# Sheet.net
KiCad netlist of a schematic drawn in Altium Designer
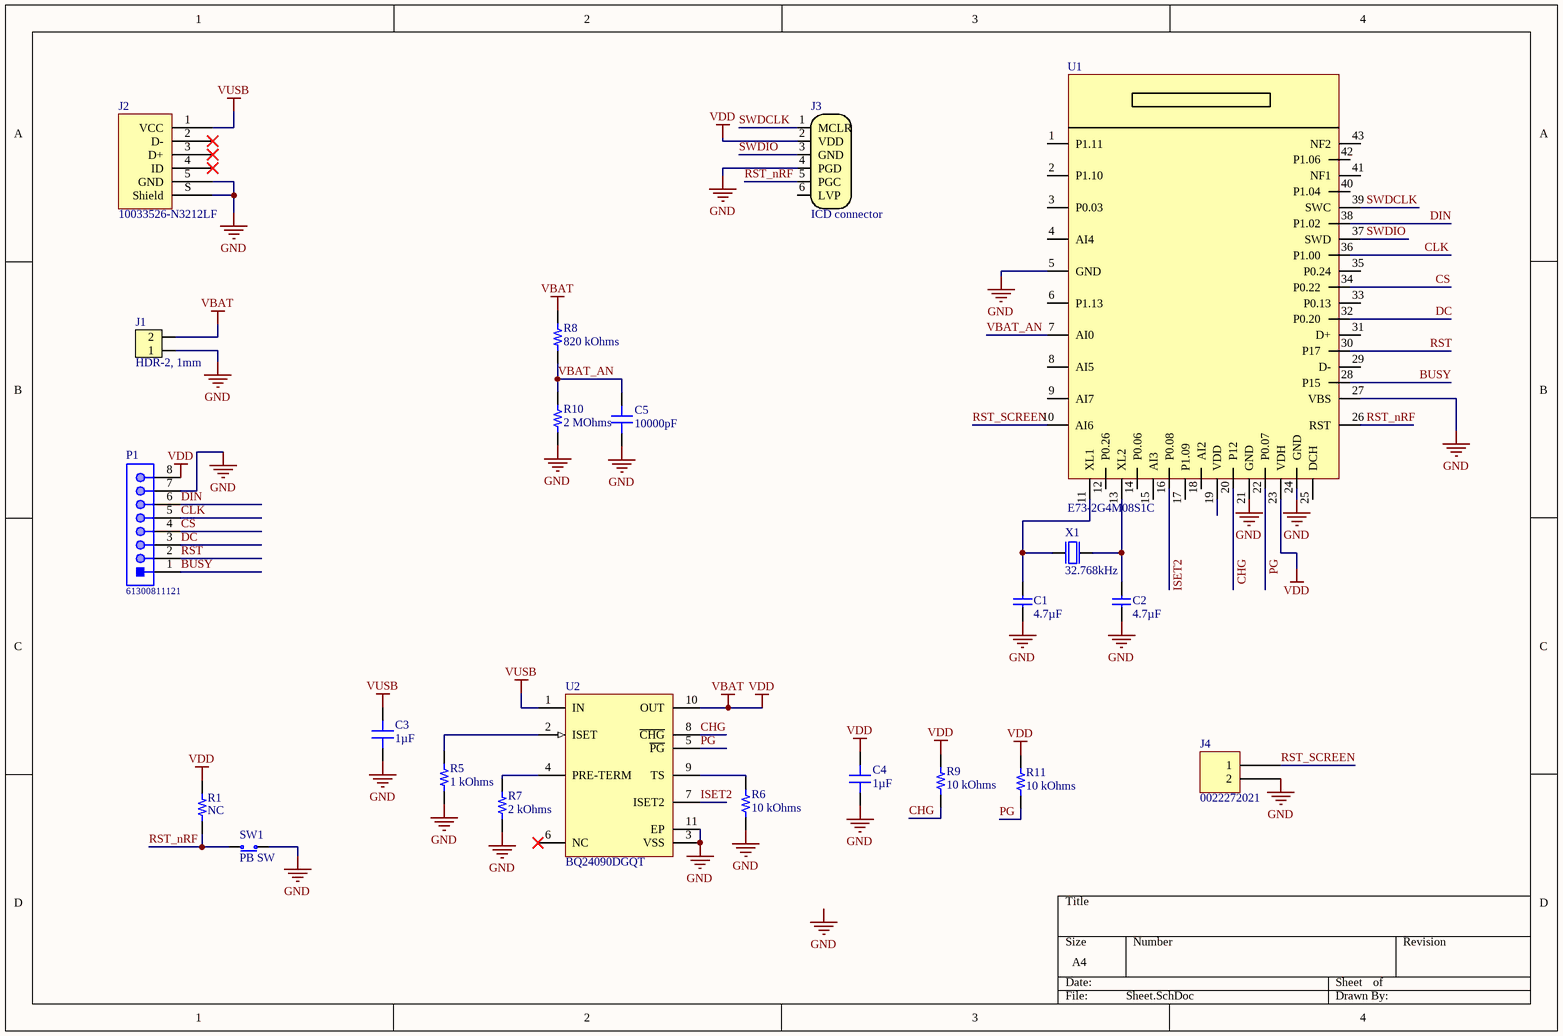
[diagram p0: Sheet.SchDoc]

(export (version "E")
  (design (tool "Eeschema 10.0.6"))
  (components
    (comp (ref "C1")
      (value "4.7µF")
      (footprint "CAPC1608X06L")
      (description "Capacitor, X7R, ±10%")
      (fields
        (field (name "PART NUMBER") "C0603-4µ7-6.3V-X7R")
        (field (name "MANUFACTURER") "Samsung")
        (field (name "PUBLISHER") "Nordic Semiconductor")
      )
      (libsource (lib "pca10056") (part "CAP_0603"))
    )
    (comp (ref "C2")
      (value "4.7µF")
      (footprint "CAPC1608X06L")
      (description "Capacitor, X7R, ±10%")
      (fields
        (field (name "PART NUMBER") "C0603-4µ7-6.3V-X7R")
        (field (name "MANUFACTURER") "Samsung")
        (field (name "PUBLISHER") "Nordic Semiconductor")
      )
      (libsource (lib "pca10056") (part "CAP_0603"))
    )
    (comp (ref "C3")
      (value "1µF")
      (footprint "CAP 0603_1608")
      (description "CAP CER 1UF 6.3V X5R 0603")
      (fields (field (name "PART NUMBER") "JMK107BJ105KK-T") (field (name "MANUFACTURER") "Taiyo Yuden"))
      (libsource (lib "Celestial Altium Library - altium_library") (part "Capacitor"))
    )
    (comp (ref "C4")
      (value "1µF")
      (footprint "CAP 0603_1608")
      (description "CAP CER 1UF 6.3V X5R 0603")
      (fields (field (name "PART NUMBER") "JMK107BJ105KK-T") (field (name "MANUFACTURER") "Taiyo Yuden"))
      (libsource (lib "Celestial Altium Library - altium_library") (part "Capacitor"))
    )
    (comp (ref "C5")
      (value "10000pF")
      (footprint "CAP 0603_1608")
      (description "CAP CER 0603 10NF 16V X7R 10%")
      (fields (field (name "PART NUMBER") "C0603C103K4RECAUTO") (field (name "MANUFACTURER") "KEMET"))
      (libsource (lib "Celestial Altium Library - altium_library") (part "Capacitor"))
    )
    (comp (ref "J1")
      (value "HDR-2, 1mm")
      (footprint "SM02B-SRSS-TB")
      (description "1.0mm pitch connector side entry SMD")
      (fields
        (field (name "PART NUMBER") "SM02B-SRSS-TB")
        (field (name "MANUFACTURER") "JST")
        (field (name "PUBLISHER") "Nordic Semiconductor")
      )
      (libsource (lib "pca10056") (part "SM02B-SRSS-TB"))
    )
    (comp (ref "J2")
      (value "10033526-N3212LF")
      (footprint "FCI USB 10033526-N3212LF")
      (description "CONN RCPT MINI USB B 5POS SMD RA")
      (fields (field (name "MANUFACTURER") "Amphenol ICC (FCI)"))
      (libsource (lib "Celestial Altium Library - altium_library") (part "USB 2.0 Type B Micro"))
    )
    (comp (ref "J3")
      (value "ICD connector")
      (footprint "TC2030-MCP-NL")
      (description "Conector par ICD")
      (libsource (lib "TC2030") (part "TC2030-MCP-NL"))
    )
    (comp (ref "J4")
      (value "0022272021")
      (footprint "MOLEX KK 0022272021")
      (description "CONN HEADER VERT 2POS 2.54MM")
      (fields (field (name "MANUFACTURER") "Molex"))
      (libsource (lib "Celestial Altium Library - altium_library") (part "2 Pin"))
    )
    (comp (ref "P1")
      (value "61300811121")
      (footprint "61300811121")
      (description "THT Vertical Pin Header WR-PHD, Pitch 2.54 mm, Single Row, 8 pins")
      (fields (field (name "MANUFACTURER") "Wurth Elektronik") (field (name "PUBLISHER") "WurthElektronik"))
      (libsource (lib "Altium Content Vault") (part "WE-CN-1P-M-R8"))
    )
    (comp (ref "R1")
      (value "NC")
      (footprint "RES 0603_1608")
      (description "RES 10K OHM 0.1% 1/16W 0603")
      (fields
        (field (name "PART NUMBER") "RNCS0603BKE10K0")
        (field (name "MANUFACTURER") "Stackpole Electronics Inc")
      )
      (libsource (lib "Celestial Altium Library - altium_library") (part "Resistor"))
    )
    (comp (ref "R5")
      (value "1 kOhms")
      (footprint "RES 0603_1608")
      (description "RES SMD 1K OHM 0.1% 1/16W 0603")
      (fields
        (field (name "PART NUMBER") "CPF0603B1K0E")
        (field (name "MANUFACTURER") "TE Connectivity Passive Product")
      )
      (libsource (lib "Celestial Altium Library - altium_library") (part "Resistor"))
    )
    (comp (ref "R6")
      (value "10 kOhms")
      (footprint "RES 0603_1608")
      (description "RES 10K OHM 0.1% 1/16W 0603")
      (fields
        (field (name "PART NUMBER") "RNCS0603BKE10K0")
        (field (name "MANUFACTURER") "Stackpole Electronics Inc")
      )
      (libsource (lib "Celestial Altium Library - altium_library") (part "Resistor"))
    )
    (comp (ref "R7")
      (value "2 kOhms")
      (footprint "RES 0603_1608")
      (description "RES SMD 2K OHM 0.1% 1/10W 0603")
      (fields (field (name "PART NUMBER") "RT0603BRD072KL") (field (name "MANUFACTURER") "Yageo"))
      (libsource (lib "Celestial Altium Library - altium_library") (part "Resistor"))
    )
    (comp (ref "R8")
      (value "820 kOhms")
      (footprint "RES 0603_1608")
      (description "CRGP 0603 820K 1%")
      (fields
        (field (name "PART NUMBER") "CRGP0603F820K")
        (field (name "MANUFACTURER") "TE Connectivity Passive Product")
      )
      (libsource (lib "Celestial Altium Library - altium_library") (part "Resistor"))
    )
    (comp (ref "R9")
      (value "10 kOhms")
      (footprint "RES 0603_1608")
      (description "RES 10K OHM 0.1% 1/16W 0603")
      (fields
        (field (name "PART NUMBER") "RNCS0603BKE10K0")
        (field (name "MANUFACTURER") "Stackpole Electronics Inc")
      )
      (libsource (lib "Celestial Altium Library - altium_library") (part "Resistor"))
    )
    (comp (ref "R10")
      (value "2 MOhms")
      (footprint "RES 0603_1608")
      (description "RES 2M OHM 1% 1/10W 0603")
      (fields
        (field (name "PART NUMBER") "RMCF0603FT2M00")
        (field (name "MANUFACTURER") "Stackpole Electronics Inc")
      )
      (libsource (lib "Celestial Altium Library - altium_library") (part "Resistor"))
    )
    (comp (ref "R11")
      (value "10 kOhms")
      (footprint "RES 0603_1608")
      (description "RES 10K OHM 0.1% 1/16W 0603")
      (fields
        (field (name "PART NUMBER") "RNCS0603BKE10K0")
        (field (name "MANUFACTURER") "Stackpole Electronics Inc")
      )
      (libsource (lib "Celestial Altium Library - altium_library") (part "Resistor"))
    )
    (comp (ref "SW1")
      (value "PB SW")
      (footprint "Switch-PB-6.2x6.3mm-SMD")
      (description "Tactile Switch, SPNO, SMD, 160gf, 6.2x6.3x2.5mm")
      (fields
        (field (name "PART NUMBER") "Switch-PB-6.2x6.3mm-SMD")
        (field (name "MANUFACTURER") "Dailywell")
        (field (name "PUBLISHER") "Nordic Semiconductor")
      )
      (libsource (lib "pca10056") (part "Switch-PB-6.2x6.3mm-SMD"))
    )
    (comp (ref "U1")
      (value "E73-2G4M08S1C")
      (footprint "E73-2G4M08S1C")
      (libsource (lib "E73-2G4M08S1C") (part "E73-2G4M08S1C"))
    )
    (comp (ref "U2")
      (value "BQ24090DGQT")
      (footprint "DGQ0010D_M")
      (fields (field (name "MANUFACTURER") "Texas Instruments"))
      (libsource (lib "Altium Content Vault") (part "TI-BQ24090DGQ10-1675X1445TP"))
    )
    (comp (ref "X1")
      (value "32.768kHz")
      (footprint "XTAL_3215")
      (description "XTAL SMD 2012, 32.768kHz, 9pF, ±20ppm")
      (fields
        (field (name "PART NUMBER") "XTAL_SMD3215_32.768kHz_9pF_NDK")
        (field (name "MANUFACTURER") "NDK")
        (field (name "PUBLISHER") "Nordic Semiconductor")
      )
      (libsource (lib "pca10056") (part "XTAL_SMD3215"))
    )
  )
  (nets
    (net (code "1") (name "/BUSY") (class "Default")
      (node (ref "P1") (pin "1") (pinfunction "1_1") (pintype "passive"))
      (node (ref "U1") (pin "28") (pinfunction "P15_28") (pintype "passive"))
    )
    (net (code "2") (name "/CHG") (class "Default")
      (node (ref "R9") (pin "2") (pinfunction "2_2") (pintype "passive"))
      (node (ref "U1") (pin "20") (pinfunction "P12_20") (pintype "passive"))
      (node (ref "U2") (pin "8") (pinfunction "~{CHG}_8") (pintype "tri_state"))
    )
    (net (code "3") (name "/CLK") (class "Default")
      (node (ref "P1") (pin "5") (pinfunction "5_5") (pintype "passive"))
      (node (ref "U1") (pin "36") (pinfunction "P1.00_36") (pintype "passive"))
    )
    (net (code "4") (name "/CS") (class "Default")
      (node (ref "P1") (pin "4") (pinfunction "4_4") (pintype "passive"))
      (node (ref "U1") (pin "34") (pinfunction "P0.22_34") (pintype "passive"))
    )
    (net (code "5") (name "/DC") (class "Default")
      (node (ref "P1") (pin "3") (pinfunction "3_3") (pintype "passive"))
      (node (ref "U1") (pin "32") (pinfunction "P0.20_32") (pintype "passive"))
    )
    (net (code "6") (name "/DIN") (class "Default")
      (node (ref "P1") (pin "6") (pinfunction "6_6") (pintype "passive"))
      (node (ref "U1") (pin "38") (pinfunction "P1.02_38") (pintype "passive"))
    )
    (net (code "7") (name "/ISET2") (class "Default")
      (node (ref "U1") (pin "16") (pinfunction "P0.08_16") (pintype "passive"))
      (node (ref "U2") (pin "7") (pinfunction "ISET2_7") (pintype "passive"))
    )
    (net (code "8") (name "/PG") (class "Default")
      (node (ref "R11") (pin "2") (pinfunction "2_2") (pintype "passive"))
      (node (ref "U1") (pin "22") (pinfunction "P0.07_22") (pintype "passive"))
      (node (ref "U2") (pin "5") (pinfunction "~{PG}_5") (pintype "tri_state"))
    )
    (net (code "9") (name "/RST") (class "Default")
      (node (ref "P1") (pin "2") (pinfunction "2_2") (pintype "passive"))
      (node (ref "U1") (pin "30") (pinfunction "P17_30") (pintype "passive"))
    )
    (net (code "10") (name "/RST_SCREEN") (class "Default")
      (node (ref "J4") (pin "1") (pinfunction "1_1") (pintype "passive"))
      (node (ref "U1") (pin "10") (pinfunction "AI6_10") (pintype "passive"))
    )
    (net (code "11") (name "/RST_nRF") (class "Default")
      (node (ref "J3") (pin "5") (pinfunction "PGC_5") (pintype "passive"))
      (node (ref "R1") (pin "1") (pinfunction "1_1") (pintype "passive"))
      (node (ref "SW1") (pin "1") (pinfunction "N.O_1") (pintype "passive"))
      (node (ref "U1") (pin "26") (pinfunction "RST_26") (pintype "passive"))
    )
    (net (code "12") (name "/SWDCLK") (class "Default")
      (node (ref "J3") (pin "1") (pinfunction "MCLR_1") (pintype "passive"))
      (node (ref "U1") (pin "39") (pinfunction "SWC_39") (pintype "passive"))
    )
    (net (code "13") (name "/SWDIO") (class "Default")
      (node (ref "J3") (pin "3") (pinfunction "GND_3") (pintype "passive"))
      (node (ref "U1") (pin "37") (pinfunction "SWD_37") (pintype "passive"))
    )
    (net (code "14") (name "/VBAT_AN") (class "Default")
      (node (ref "C5") (pin "2") (pinfunction "2_2") (pintype "passive"))
      (node (ref "R10") (pin "2") (pinfunction "2_2") (pintype "passive"))
      (node (ref "R8") (pin "1") (pinfunction "1_1") (pintype "passive"))
      (node (ref "U1") (pin "7") (pinfunction "AI0_7") (pintype "passive"))
    )
    (net (code "15") (name "GND") (class "Default")
      (node (ref "C1") (pin "1") (pinfunction "1_1") (pintype "passive"))
      (node (ref "C2") (pin "1") (pinfunction "1_1") (pintype "passive"))
      (node (ref "C3") (pin "1") (pinfunction "1_1") (pintype "passive"))
      (node (ref "C4") (pin "1") (pinfunction "1_1") (pintype "passive"))
      (node (ref "C5") (pin "1") (pinfunction "1_1") (pintype "passive"))
      (node (ref "J1") (pin "1") (pinfunction "1_1") (pintype "passive"))
      (node (ref "J2") (pin "5") (pinfunction "GND_5") (pintype "passive"))
      (node (ref "J2") (pin "S") (pinfunction "Shield_S") (pintype "passive"))
      (node (ref "J3") (pin "4") (pinfunction "PGD_4") (pintype "passive"))
      (node (ref "J4") (pin "2") (pinfunction "2_2") (pintype "passive"))
      (node (ref "P1") (pin "7") (pinfunction "7_7") (pintype "passive"))
      (node (ref "R10") (pin "1") (pinfunction "1_1") (pintype "passive"))
      (node (ref "R5") (pin "1") (pinfunction "1_1") (pintype "passive"))
      (node (ref "R6") (pin "1") (pinfunction "1_1") (pintype "passive"))
      (node (ref "R7") (pin "1") (pinfunction "1_1") (pintype "passive"))
      (node (ref "SW1") (pin "2") (pinfunction "COM_2") (pintype "passive"))
      (node (ref "U1") (pin "21") (pinfunction "GND_21") (pintype "passive"))
      (node (ref "U1") (pin "24") (pinfunction "GND_24") (pintype "passive"))
      (node (ref "U1") (pin "27") (pinfunction "VBS_27") (pintype "passive"))
      (node (ref "U1") (pin "5") (pinfunction "GND_5") (pintype "passive"))
      (node (ref "U2") (pin "11") (pinfunction "EP_11") (pintype "power_in"))
      (node (ref "U2") (pin "3") (pinfunction "VSS_3") (pintype "power_in"))
    )
    (net (code "16") (name "Net-(U1-XL1)") (class "Default")
      (node (ref "C1") (pin "2") (pinfunction "2_2") (pintype "passive"))
      (node (ref "U1") (pin "11") (pinfunction "XL1_11") (pintype "passive"))
      (node (ref "X1") (pin "1") (pinfunction "inp_1") (pintype "passive"))
    )
    (net (code "17") (name "Net-(U1-XL2)") (class "Default")
      (node (ref "C2") (pin "2") (pinfunction "2_2") (pintype "passive"))
      (node (ref "U1") (pin "13") (pinfunction "XL2_13") (pintype "passive"))
      (node (ref "X1") (pin "2") (pinfunction "out_2") (pintype "passive"))
    )
    (net (code "18") (name "Net-(U2-ISET)") (class "Default")
      (node (ref "R5") (pin "2") (pinfunction "2_2") (pintype "passive"))
      (node (ref "U2") (pin "2") (pinfunction "ISET_2") (pintype "input"))
    )
    (net (code "19") (name "Net-(U2-PRE-TERM)") (class "Default")
      (node (ref "R7") (pin "2") (pinfunction "2_2") (pintype "passive"))
      (node (ref "U2") (pin "4") (pinfunction "PRE-TERM_4") (pintype "passive"))
    )
    (net (code "20") (name "Net-(U2-TS)") (class "Default")
      (node (ref "R6") (pin "2") (pinfunction "2_2") (pintype "passive"))
      (node (ref "U2") (pin "9") (pinfunction "TS_9") (pintype "passive"))
    )
    (net (code "21") (name "VBAT") (class "Default")
      (node (ref "C4") (pin "2") (pinfunction "2_2") (pintype "passive"))
      (node (ref "J1") (pin "2") (pinfunction "2_2") (pintype "passive"))
      (node (ref "J3") (pin "2") (pinfunction "VDD_2") (pintype "passive"))
      (node (ref "P1") (pin "8") (pinfunction "8_8") (pintype "passive"))
      (node (ref "R1") (pin "2") (pinfunction "2_2") (pintype "passive"))
      (node (ref "R11") (pin "1") (pinfunction "1_1") (pintype "passive"))
      (node (ref "R8") (pin "2") (pinfunction "2_2") (pintype "passive"))
      (node (ref "R9") (pin "1") (pinfunction "1_1") (pintype "passive"))
      (node (ref "U1") (pin "23") (pinfunction "VDH_23") (pintype "passive"))
      (node (ref "U2") (pin "10") (pinfunction "OUT_10") (pintype "power_in"))
    )
    (net (code "22") (name "VUSB") (class "Default")
      (node (ref "C3") (pin "2") (pinfunction "2_2") (pintype "passive"))
      (node (ref "J2") (pin "1") (pinfunction "VCC_1") (pintype "passive"))
      (node (ref "U2") (pin "1") (pinfunction "IN_1") (pintype "power_in"))
    )
    (net (code "23") (name "unconnected-(J2-D+-Pad3)") (class "Default")
      (node (ref "J2") (pin "3") (pinfunction "D+_3") (pintype "passive+no_connect"))
    )
    (net (code "24") (name "unconnected-(J2-D--Pad2)") (class "Default")
      (node (ref "J2") (pin "2") (pinfunction "D-_2") (pintype "passive+no_connect"))
    )
    (net (code "25") (name "unconnected-(J2-ID-Pad4)") (class "Default")
      (node (ref "J2") (pin "4") (pinfunction "ID_4") (pintype "passive+no_connect"))
    )
    (net (code "26") (name "unconnected-(J3-LVP-Pad6)") (class "Default")
      (node (ref "J3") (pin "6") (pinfunction "LVP_6") (pintype "passive"))
    )
    (net (code "27") (name "unconnected-(U1-AI2-Pad18)") (class "Default")
      (node (ref "U1") (pin "18") (pinfunction "AI2_18") (pintype "passive"))
    )
    (net (code "28") (name "unconnected-(U1-AI3-Pad15)") (class "Default")
      (node (ref "U1") (pin "15") (pinfunction "AI3_15") (pintype "passive"))
    )
    (net (code "29") (name "unconnected-(U1-AI4-Pad4)") (class "Default")
      (node (ref "U1") (pin "4") (pinfunction "AI4_4") (pintype "passive"))
    )
    (net (code "30") (name "unconnected-(U1-AI5-Pad8)") (class "Default")
      (node (ref "U1") (pin "8") (pinfunction "AI5_8") (pintype "passive"))
    )
    (net (code "31") (name "unconnected-(U1-AI7-Pad9)") (class "Default")
      (node (ref "U1") (pin "9") (pinfunction "AI7_9") (pintype "passive"))
    )
    (net (code "32") (name "unconnected-(U1-D+-Pad31)") (class "Default")
      (node (ref "U1") (pin "31") (pinfunction "D+_31") (pintype "passive"))
    )
    (net (code "33") (name "unconnected-(U1-D--Pad29)") (class "Default")
      (node (ref "U1") (pin "29") (pinfunction "D-_29") (pintype "passive"))
    )
    (net (code "34") (name "unconnected-(U1-DCH-Pad25)") (class "Default")
      (node (ref "U1") (pin "25") (pinfunction "DCH_25") (pintype "passive"))
    )
    (net (code "35") (name "unconnected-(U1-NF1-Pad41)") (class "Default")
      (node (ref "U1") (pin "41") (pinfunction "NF1_41") (pintype "passive"))
    )
    (net (code "36") (name "unconnected-(U1-NF2-Pad43)") (class "Default")
      (node (ref "U1") (pin "43") (pinfunction "NF2_43") (pintype "passive"))
    )
    (net (code "37") (name "unconnected-(U1-P0.03-Pad3)") (class "Default")
      (node (ref "U1") (pin "3") (pinfunction "P0.03_3") (pintype "passive"))
    )
    (net (code "38") (name "unconnected-(U1-P0.06-Pad14)") (class "Default")
      (node (ref "U1") (pin "14") (pinfunction "P0.06_14") (pintype "passive"))
    )
    (net (code "39") (name "unconnected-(U1-P0.13-Pad33)") (class "Default")
      (node (ref "U1") (pin "33") (pinfunction "P0.13_33") (pintype "passive"))
    )
    (net (code "40") (name "unconnected-(U1-P0.24-Pad35)") (class "Default")
      (node (ref "U1") (pin "35") (pinfunction "P0.24_35") (pintype "passive"))
    )
    (net (code "41") (name "unconnected-(U1-P0.26-Pad12)") (class "Default")
      (node (ref "U1") (pin "12") (pinfunction "P0.26_12") (pintype "passive"))
    )
    (net (code "42") (name "unconnected-(U1-P1.04-Pad40)") (class "Default")
      (node (ref "U1") (pin "40") (pinfunction "P1.04_40") (pintype "passive"))
    )
    (net (code "43") (name "unconnected-(U1-P1.06-Pad42)") (class "Default")
      (node (ref "U1") (pin "42") (pinfunction "P1.06_42") (pintype "passive"))
    )
    (net (code "44") (name "unconnected-(U1-P1.09-Pad17)") (class "Default")
      (node (ref "U1") (pin "17") (pinfunction "P1.09_17") (pintype "passive"))
    )
    (net (code "45") (name "unconnected-(U1-P1.10-Pad2)") (class "Default")
      (node (ref "U1") (pin "2") (pinfunction "P1.10_2") (pintype "passive"))
    )
    (net (code "46") (name "unconnected-(U1-P1.11-Pad1)") (class "Default")
      (node (ref "U1") (pin "1") (pinfunction "P1.11_1") (pintype "passive"))
    )
    (net (code "47") (name "unconnected-(U1-P1.13-Pad6)") (class "Default")
      (node (ref "U1") (pin "6") (pinfunction "P1.13_6") (pintype "passive"))
    )
    (net (code "48") (name "unconnected-(U1-VDD-Pad19)") (class "Default")
      (node (ref "U1") (pin "19") (pinfunction "VDD_19") (pintype "passive"))
    )
    (net (code "49") (name "unconnected-(U2-NC-Pad6)") (class "Default")
      (node (ref "U2") (pin "6") (pinfunction "NC_6") (pintype "passive+no_connect"))
    )
  )
)
